# od855.net
KiCad netlist of a schematic drawn in EAGLE
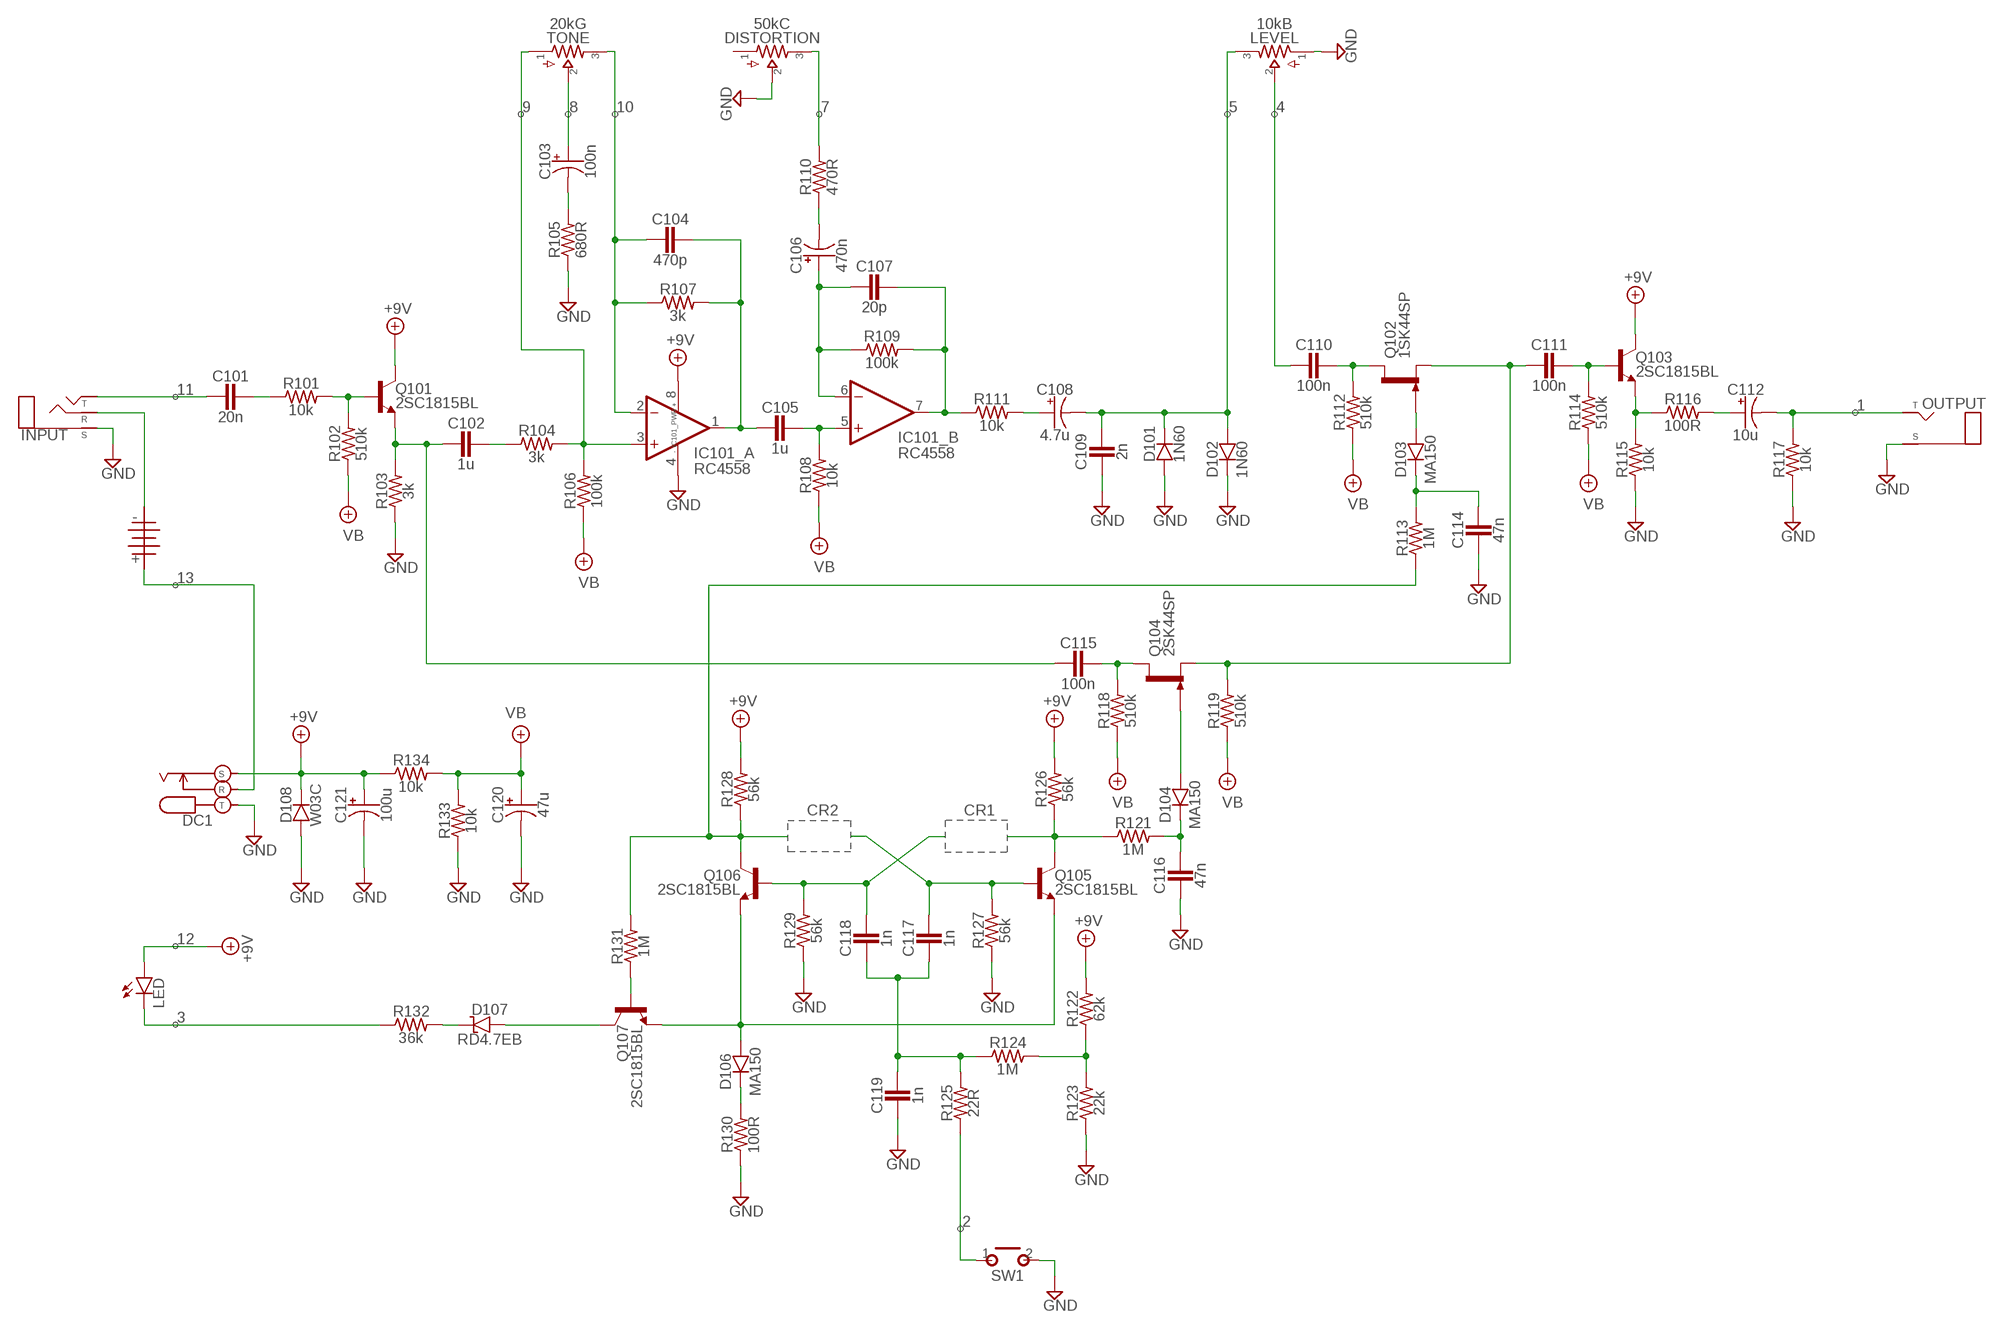
[diagram p0: schematic, sheet 1]

(export (version "E")
  (design (tool "Eeschema 10.0.6"))
  (components
    (comp (ref "11")
      (value "BATTERY")
      (footprint "eagle-import:TWO_PADS")
      (libsource (lib "eagle-import") (part "BATTERY"))
    )
    (comp (ref "C101")
      (value "20n")
      (footprint "eagle-import:BOX_SMALL")
      (libsource (lib "eagle-import") (part "CER/FILMBOX.1"))
    )
    (comp (ref "C102")
      (value "1u")
      (footprint "eagle-import:BOX_SMALL")
      (libsource (lib "eagle-import") (part "CER/FILMBOX.1"))
    )
    (comp (ref "C103")
      (value "100n")
      (footprint "eagle-import:050_020")
      (libsource (lib "eagle-import") (part "0500"))
    )
    (comp (ref "C104")
      (value "470p")
      (footprint "eagle-import:BOX_SMALL")
      (libsource (lib "eagle-import") (part "CER/FILMBOX.1"))
    )
    (comp (ref "C105")
      (value "1u")
      (footprint "eagle-import:BOX_SMALL")
      (libsource (lib "eagle-import") (part "CER/FILMBOX.1"))
    )
    (comp (ref "C106")
      (value "470n")
      (footprint "eagle-import:050_020")
      (libsource (lib "eagle-import") (part "0500"))
    )
    (comp (ref "C107")
      (value "20p")
      (footprint "eagle-import:BOX_SMALL")
      (libsource (lib "eagle-import") (part "CER/FILMBOX.1"))
    )
    (comp (ref "C108")
      (value "4.7u")
      (footprint "eagle-import:050_020")
      (libsource (lib "eagle-import") (part "0500"))
    )
    (comp (ref "C109")
      (value "2n")
      (footprint "eagle-import:BOX_SMALL")
      (libsource (lib "eagle-import") (part "CER/FILMBOX.1"))
    )
    (comp (ref "C110")
      (value "100n")
      (footprint "eagle-import:BOX_SMALL")
      (libsource (lib "eagle-import") (part "CER/FILMBOX.1"))
    )
    (comp (ref "C111")
      (value "100n")
      (footprint "eagle-import:BOX_SMALL")
      (libsource (lib "eagle-import") (part "CER/FILMBOX.1"))
    )
    (comp (ref "C112")
      (value "10u")
      (footprint "eagle-import:050_020")
      (libsource (lib "eagle-import") (part "0500"))
    )
    (comp (ref "C114")
      (value "47n")
      (footprint "eagle-import:BOX_SMALL")
      (libsource (lib "eagle-import") (part "CER/FILMBOX.1"))
    )
    (comp (ref "C115")
      (value "100n")
      (footprint "eagle-import:BOX_SMALL")
      (libsource (lib "eagle-import") (part "CER/FILMBOX.1"))
    )
    (comp (ref "C116")
      (value "47n")
      (footprint "eagle-import:BOX_SMALL")
      (libsource (lib "eagle-import") (part "CER/FILMBOX.1"))
    )
    (comp (ref "C117")
      (value "1n")
      (footprint "eagle-import:BOX_SMALL")
      (libsource (lib "eagle-import") (part "CER/FILMBOX.1"))
    )
    (comp (ref "C118")
      (value "1n")
      (footprint "eagle-import:BOX_SMALL")
      (libsource (lib "eagle-import") (part "CER/FILMBOX.1"))
    )
    (comp (ref "C119")
      (value "1n")
      (footprint "eagle-import:BOX_SMALL")
      (libsource (lib "eagle-import") (part "CER/FILMBOX.1"))
    )
    (comp (ref "C120")
      (value "47u")
      (footprint "eagle-import:050_020")
      (libsource (lib "eagle-import") (part "0500"))
    )
    (comp (ref "C121")
      (value "100u")
      (footprint "eagle-import:050_020")
      (libsource (lib "eagle-import") (part "0500"))
    )
    (comp (ref "D101")
      (value "1N60")
      (footprint "eagle-import:DO35-2")
      (libsource (lib "eagle-import") (part "DO35.2"))
    )
    (comp (ref "D102")
      (value "1N60")
      (footprint "eagle-import:DO35-2")
      (libsource (lib "eagle-import") (part "DO35.2"))
    )
    (comp (ref "D103")
      (value "MA150")
      (footprint "eagle-import:DO35-2")
      (libsource (lib "eagle-import") (part "DO35.2"))
    )
    (comp (ref "D104")
      (value "MA150")
      (footprint "eagle-import:DO35-2")
      (libsource (lib "eagle-import") (part "DO35.2"))
    )
    (comp (ref "D106")
      (value "MA150")
      (footprint "eagle-import:DO35-2")
      (libsource (lib "eagle-import") (part "DO35.2"))
    )
    (comp (ref "D107")
      (value "RD4.7EB")
      (footprint "eagle-import:DO41-2")
      (libsource (lib "eagle-import") (part "ZENER.2"))
    )
    (comp (ref "D108")
      (value "W03C")
      (footprint "eagle-import:DO35-2")
      (libsource (lib "eagle-import") (part "DO35.2"))
    )
    (comp (ref "DC1")
      (value "DCJACK")
      (footprint "eagle-import:DC_KOBICONN")
      (libsource (lib "eagle-import") (part "DC_KOBICONN"))
    )
    (comp (ref "DISTORTION")
      (value "50kC")
      (footprint "eagle-import:16MM")
      (libsource (lib "eagle-import") (part "POTS16MM"))
    )
    (comp (ref "IC101")
      (value "RC4558")
      (footprint "eagle-import:DIL0")
      (libsource (lib "eagle-import") (part "DUALTH"))
    )
    (comp (ref "INPUT")
      (value "STEREO3PADS")
      (footprint "eagle-import:THREEPADS")
      (libsource (lib "eagle-import") (part "STEREO3PADS"))
    )
    (comp (ref "LED")
      (value "LED")
      (footprint "eagle-import:3MM_D")
      (libsource (lib "eagle-import") (part "LED"))
    )
    (comp (ref "LEVEL")
      (value "10kB")
      (footprint "eagle-import:16MM")
      (libsource (lib "eagle-import") (part "POTS16MM"))
    )
    (comp (ref "OUTPUT")
      (value "MONO")
      (footprint "eagle-import:TWO_PADS")
      (libsource (lib "eagle-import") (part "MONO"))
    )
    (comp (ref "Q101")
      (value "2SC1815BL")
      (footprint "eagle-import:TO92-")
      (libsource (lib "eagle-import") (part "2N3904"))
    )
    (comp (ref "Q102")
      (value "1SK44SP")
      (footprint "eagle-import:TO92-")
      (libsource (lib "eagle-import") (part "2N5457"))
    )
    (comp (ref "Q103")
      (value "2SC1815BL")
      (footprint "eagle-import:TO92-")
      (libsource (lib "eagle-import") (part "2N3904"))
    )
    (comp (ref "Q104")
      (value "2SK44SP")
      (footprint "eagle-import:TO92-")
      (libsource (lib "eagle-import") (part "2N5457"))
    )
    (comp (ref "Q105")
      (value "2SC1815BL")
      (footprint "eagle-import:TO92-")
      (libsource (lib "eagle-import") (part "2SC828A"))
    )
    (comp (ref "Q106")
      (value "2SC1815BL")
      (footprint "eagle-import:TO92-")
      (libsource (lib "eagle-import") (part "2SC828A"))
    )
    (comp (ref "Q107")
      (value "2SC1815BL")
      (footprint "eagle-import:TO92-")
      (libsource (lib "eagle-import") (part "2SC828A"))
    )
    (comp (ref "R101")
      (value "10k")
      (footprint "eagle-import:R0207_3")
      (libsource (lib "eagle-import") (part "R_.3B"))
    )
    (comp (ref "R102")
      (value "510k")
      (footprint "eagle-import:R0207_3")
      (libsource (lib "eagle-import") (part "R_.3B"))
    )
    (comp (ref "R103")
      (value "3k")
      (footprint "eagle-import:R0207_3")
      (libsource (lib "eagle-import") (part "R_.3B"))
    )
    (comp (ref "R104")
      (value "3k")
      (footprint "eagle-import:R0207_3")
      (libsource (lib "eagle-import") (part "R_.3B"))
    )
    (comp (ref "R105")
      (value "680R")
      (footprint "eagle-import:R0207_3")
      (libsource (lib "eagle-import") (part "R_.3B"))
    )
    (comp (ref "R106")
      (value "100k")
      (footprint "eagle-import:R0207_3")
      (libsource (lib "eagle-import") (part "R_.3B"))
    )
    (comp (ref "R107")
      (value "3k")
      (footprint "eagle-import:R0207_3")
      (libsource (lib "eagle-import") (part "R_.3B"))
    )
    (comp (ref "R108")
      (value "10k")
      (footprint "eagle-import:R0207_3")
      (libsource (lib "eagle-import") (part "R_.3B"))
    )
    (comp (ref "R109")
      (value "100k")
      (footprint "eagle-import:R0207_3")
      (libsource (lib "eagle-import") (part "R_.3B"))
    )
    (comp (ref "R110")
      (value "470R")
      (footprint "eagle-import:R0207_3")
      (libsource (lib "eagle-import") (part "R_.3B"))
    )
    (comp (ref "R111")
      (value "10k")
      (footprint "eagle-import:R0207_3")
      (libsource (lib "eagle-import") (part "R_.3B"))
    )
    (comp (ref "R112")
      (value "510k")
      (footprint "eagle-import:R0207_3")
      (libsource (lib "eagle-import") (part "R_.3B"))
    )
    (comp (ref "R113")
      (value "1M")
      (footprint "eagle-import:R0207_3")
      (libsource (lib "eagle-import") (part "R_.3B"))
    )
    (comp (ref "R114")
      (value "510k")
      (footprint "eagle-import:R0207_3")
      (libsource (lib "eagle-import") (part "R_.3B"))
    )
    (comp (ref "R115")
      (value "10k")
      (footprint "eagle-import:R0207_3")
      (libsource (lib "eagle-import") (part "R_.3B"))
    )
    (comp (ref "R116")
      (value "100R")
      (footprint "eagle-import:R0207_3")
      (libsource (lib "eagle-import") (part "R_.3B"))
    )
    (comp (ref "R117")
      (value "10k")
      (footprint "eagle-import:R0207_3")
      (libsource (lib "eagle-import") (part "R_.3B"))
    )
    (comp (ref "R118")
      (value "510k")
      (footprint "eagle-import:R0207_3")
      (libsource (lib "eagle-import") (part "R_.3B"))
    )
    (comp (ref "R119")
      (value "510k")
      (footprint "eagle-import:R0207_3")
      (libsource (lib "eagle-import") (part "R_.3B"))
    )
    (comp (ref "R121")
      (value "1M")
      (footprint "eagle-import:R0207_3")
      (libsource (lib "eagle-import") (part "R_.3B"))
    )
    (comp (ref "R122")
      (value "62k")
      (footprint "eagle-import:R0207_3")
      (libsource (lib "eagle-import") (part "R_.3B"))
    )
    (comp (ref "R123")
      (value "22k")
      (footprint "eagle-import:R0207_3")
      (libsource (lib "eagle-import") (part "R_.3B"))
    )
    (comp (ref "R124")
      (value "1M")
      (footprint "eagle-import:R0207_3")
      (libsource (lib "eagle-import") (part "R_.3B"))
    )
    (comp (ref "R125")
      (value "22R")
      (footprint "eagle-import:R0207_3")
      (libsource (lib "eagle-import") (part "R_.3B"))
    )
    (comp (ref "R126")
      (value "56k")
      (footprint "eagle-import:R0207_3")
      (libsource (lib "eagle-import") (part "R_.3B"))
    )
    (comp (ref "R127")
      (value "56k")
      (footprint "eagle-import:R0207_3")
      (libsource (lib "eagle-import") (part "R_.3B"))
    )
    (comp (ref "R128")
      (value "56k")
      (footprint "eagle-import:R0207_3")
      (libsource (lib "eagle-import") (part "R_.3B"))
    )
    (comp (ref "R129")
      (value "56k")
      (footprint "eagle-import:R0207_3")
      (libsource (lib "eagle-import") (part "R_.3B"))
    )
    (comp (ref "R130")
      (value "100R")
      (footprint "eagle-import:R0207_3")
      (libsource (lib "eagle-import") (part "R_.3B"))
    )
    (comp (ref "R131")
      (value "1M")
      (footprint "eagle-import:R0207_3")
      (libsource (lib "eagle-import") (part "R_.3B"))
    )
    (comp (ref "R132")
      (value "36k")
      (footprint "eagle-import:R0207_3")
      (libsource (lib "eagle-import") (part "R_.3B"))
    )
    (comp (ref "R133")
      (value "10k")
      (footprint "eagle-import:R0207_3")
      (libsource (lib "eagle-import") (part "R_.3B"))
    )
    (comp (ref "R134")
      (value "10k")
      (footprint "eagle-import:R0207_3")
      (libsource (lib "eagle-import") (part "R_.3B"))
    )
    (comp (ref "SW1")
      (value "MOMENTARY")
      (footprint "eagle-import:SPST")
      (libsource (lib "eagle-import") (part "MOMENTARY"))
    )
    (comp (ref "TONE")
      (value "20kG")
      (footprint "eagle-import:16MM")
      (libsource (lib "eagle-import") (part "POTS16MM"))
    )
  )
  (nets
    (net (code "1") (name "+9V") (class "Default")
      (node (ref "C121") (pin "+") (pinfunction "+_+") (pintype "passive"))
      (node (ref "D108") (pin "C") (pinfunction "C_C") (pintype "passive"))
      (node (ref "DC1") (pin "S") (pinfunction "S_S") (pintype "bidirectional"))
      (node (ref "IC101") (pin "8") (pinfunction "V+_8") (pintype "power_in"))
      (node (ref "LED") (pin "ANODE") (pinfunction "A_ANODE") (pintype "passive"))
      (node (ref "Q101") (pin "1") (pinfunction "C_1") (pintype "passive"))
      (node (ref "Q103") (pin "1") (pinfunction "C_1") (pintype "passive"))
      (node (ref "R122") (pin "2") (pinfunction "2_2") (pintype "passive"))
      (node (ref "R126") (pin "2") (pinfunction "2_2") (pintype "passive"))
      (node (ref "R128") (pin "2") (pinfunction "2_2") (pintype "passive"))
      (node (ref "R134") (pin "1") (pinfunction "1_1") (pintype "passive"))
    )
    (net (code "2") (name "GND") (class "Default")
      (node (ref "C109") (pin "2") (pinfunction "2_2") (pintype "passive"))
      (node (ref "C114") (pin "2") (pinfunction "2_2") (pintype "passive"))
      (node (ref "C116") (pin "2") (pinfunction "2_2") (pintype "passive"))
      (node (ref "C119") (pin "2") (pinfunction "2_2") (pintype "passive"))
      (node (ref "C120") (pin "-") (pinfunction "-_-") (pintype "passive"))
      (node (ref "C121") (pin "-") (pinfunction "-_-") (pintype "passive"))
      (node (ref "D101") (pin "A") (pinfunction "A_A") (pintype "passive"))
      (node (ref "D102") (pin "C") (pinfunction "C_C") (pintype "passive"))
      (node (ref "D108") (pin "A") (pinfunction "A_A") (pintype "passive"))
      (node (ref "DC1") (pin "T") (pinfunction "T_T") (pintype "bidirectional"))
      (node (ref "DISTORTION") (pin "2") (pinfunction "2_2") (pintype "passive"))
      (node (ref "IC101") (pin "4") (pinfunction "V-_4") (pintype "power_in"))
      (node (ref "INPUT") (pin "SLEEVE") (pinfunction "S_SLEEVE") (pintype "passive"))
      (node (ref "LEVEL") (pin "1") (pinfunction "1_1") (pintype "passive"))
      (node (ref "OUTPUT") (pin "S") (pinfunction "SLEEVE_S") (pintype "passive"))
      (node (ref "R103") (pin "1") (pinfunction "1_1") (pintype "passive"))
      (node (ref "R105") (pin "1") (pinfunction "1_1") (pintype "passive"))
      (node (ref "R115") (pin "1") (pinfunction "1_1") (pintype "passive"))
      (node (ref "R117") (pin "1") (pinfunction "1_1") (pintype "passive"))
      (node (ref "R123") (pin "1") (pinfunction "1_1") (pintype "passive"))
      (node (ref "R127") (pin "1") (pinfunction "1_1") (pintype "passive"))
      (node (ref "R129") (pin "1") (pinfunction "1_1") (pintype "passive"))
      (node (ref "R130") (pin "1") (pinfunction "1_1") (pintype "passive"))
      (node (ref "R133") (pin "1") (pinfunction "1_1") (pintype "passive"))
      (node (ref "SW1") (pin "2") (pinfunction "S_2") (pintype "passive"))
    )
    (net (code "3") (name "Net-(11-P$1)") (class "Default")
      (node (ref "11") (pin "T") (pinfunction "P$1_T") (pintype "bidirectional"))
      (node (ref "DC1") (pin "R") (pinfunction "R_R") (pintype "bidirectional"))
    )
    (net (code "4") (name "Net-(11-P$2)") (class "Default")
      (node (ref "11") (pin "S") (pinfunction "P$2_S") (pintype "bidirectional"))
      (node (ref "INPUT") (pin "RING") (pinfunction "R_RING") (pintype "passive"))
    )
    (net (code "5") (name "Net-(C101-Pad1)") (class "Default")
      (node (ref "C101") (pin "1") (pinfunction "1_1") (pintype "passive"))
      (node (ref "R101") (pin "1") (pinfunction "1_1") (pintype "passive"))
    )
    (net (code "6") (name "Net-(C102-Pad1)") (class "Default")
      (node (ref "C102") (pin "1") (pinfunction "1_1") (pintype "passive"))
      (node (ref "R104") (pin "1") (pinfunction "1_1") (pintype "passive"))
    )
    (net (code "7") (name "Net-(C103-Pad+)") (class "Default")
      (node (ref "C103") (pin "+") (pinfunction "+_+") (pintype "passive"))
      (node (ref "TONE") (pin "2") (pinfunction "2_2") (pintype "passive"))
    )
    (net (code "8") (name "Net-(C103-Pad-)") (class "Default")
      (node (ref "C103") (pin "-") (pinfunction "-_-") (pintype "passive"))
      (node (ref "R105") (pin "2") (pinfunction "2_2") (pintype "passive"))
    )
    (net (code "9") (name "Net-(C106-Pad-)") (class "Default")
      (node (ref "C106") (pin "-") (pinfunction "-_-") (pintype "passive"))
      (node (ref "R110") (pin "1") (pinfunction "1_1") (pintype "passive"))
    )
    (net (code "10") (name "Net-(C108-Pad+)") (class "Default")
      (node (ref "C108") (pin "+") (pinfunction "+_+") (pintype "passive"))
      (node (ref "R111") (pin "2") (pinfunction "2_2") (pintype "passive"))
    )
    (net (code "11") (name "Net-(C108-Pad-)") (class "Default")
      (node (ref "C108") (pin "-") (pinfunction "-_-") (pintype "passive"))
      (node (ref "C109") (pin "1") (pinfunction "1_1") (pintype "passive"))
      (node (ref "D101") (pin "C") (pinfunction "C_C") (pintype "passive"))
      (node (ref "D102") (pin "A") (pinfunction "A_A") (pintype "passive"))
      (node (ref "LEVEL") (pin "3") (pinfunction "3_3") (pintype "passive"))
    )
    (net (code "12") (name "Net-(C110-Pad2)") (class "Default")
      (node (ref "C110") (pin "2") (pinfunction "2_2") (pintype "passive"))
      (node (ref "LEVEL") (pin "2") (pinfunction "2_2") (pintype "passive"))
    )
    (net (code "13") (name "Net-(C112-Pad+)") (class "Default")
      (node (ref "C112") (pin "+") (pinfunction "+_+") (pintype "passive"))
      (node (ref "R116") (pin "2") (pinfunction "2_2") (pintype "passive"))
    )
    (net (code "14") (name "Net-(C114-Pad1)") (class "Default")
      (node (ref "C114") (pin "1") (pinfunction "1_1") (pintype "passive"))
      (node (ref "D103") (pin "C") (pinfunction "C_C") (pintype "passive"))
      (node (ref "R113") (pin "2") (pinfunction "2_2") (pintype "passive"))
    )
    (net (code "15") (name "Net-(C116-Pad1)") (class "Default")
      (node (ref "C116") (pin "1") (pinfunction "1_1") (pintype "passive"))
      (node (ref "D104") (pin "C") (pinfunction "C_C") (pintype "passive"))
      (node (ref "R121") (pin "2") (pinfunction "2_2") (pintype "passive"))
    )
    (net (code "16") (name "Net-(C117-Pad2)") (class "Default")
      (node (ref "C117") (pin "2") (pinfunction "2_2") (pintype "passive"))
      (node (ref "C118") (pin "2") (pinfunction "2_2") (pintype "passive"))
      (node (ref "C119") (pin "1") (pinfunction "1_1") (pintype "passive"))
      (node (ref "R124") (pin "1") (pinfunction "1_1") (pintype "passive"))
      (node (ref "R125") (pin "2") (pinfunction "2_2") (pintype "passive"))
    )
    (net (code "17") (name "Net-(D106-PadC)") (class "Default")
      (node (ref "D106") (pin "C") (pinfunction "C_C") (pintype "passive"))
      (node (ref "R130") (pin "2") (pinfunction "2_2") (pintype "passive"))
    )
    (net (code "18") (name "Net-(D107-PadC)") (class "Default")
      (node (ref "D107") (pin "C") (pinfunction "C_C") (pintype "passive"))
      (node (ref "R132") (pin "2") (pinfunction "2_2") (pintype "passive"))
    )
    (net (code "19") (name "Net-(DISTORTION-Pad3)") (class "Default")
      (node (ref "DISTORTION") (pin "3") (pinfunction "3_3") (pintype "passive"))
      (node (ref "R110") (pin "2") (pinfunction "2_2") (pintype "passive"))
    )
    (net (code "20") (name "Net-(IC101A-+IN)") (class "Default")
      (node (ref "IC101") (pin "3") (pinfunction "+IN_3") (pintype "input"))
      (node (ref "R104") (pin "2") (pinfunction "2_2") (pintype "passive"))
      (node (ref "R106") (pin "2") (pinfunction "2_2") (pintype "passive"))
      (node (ref "TONE") (pin "1") (pinfunction "1_1") (pintype "passive"))
    )
    (net (code "21") (name "Net-(IC101A--IN)") (class "Default")
      (node (ref "C104") (pin "2") (pinfunction "2_2") (pintype "passive"))
      (node (ref "IC101") (pin "2") (pinfunction "-IN_2") (pintype "input"))
      (node (ref "R107") (pin "1") (pinfunction "1_1") (pintype "passive"))
      (node (ref "TONE") (pin "3") (pinfunction "3_3") (pintype "passive"))
    )
    (net (code "22") (name "Net-(IC101A-OUT)") (class "Default")
      (node (ref "C104") (pin "1") (pinfunction "1_1") (pintype "passive"))
      (node (ref "C105") (pin "2") (pinfunction "2_2") (pintype "passive"))
      (node (ref "IC101") (pin "1") (pinfunction "OUT_1") (pintype "output"))
      (node (ref "R107") (pin "2") (pinfunction "2_2") (pintype "passive"))
    )
    (net (code "23") (name "Net-(IC101B-+IN)") (class "Default")
      (node (ref "C105") (pin "1") (pinfunction "1_1") (pintype "passive"))
      (node (ref "IC101") (pin "5") (pinfunction "+IN_5") (pintype "input"))
      (node (ref "R108") (pin "2") (pinfunction "2_2") (pintype "passive"))
    )
    (net (code "24") (name "Net-(IC101B--IN)") (class "Default")
      (node (ref "C106") (pin "+") (pinfunction "+_+") (pintype "passive"))
      (node (ref "C107") (pin "2") (pinfunction "2_2") (pintype "passive"))
      (node (ref "IC101") (pin "6") (pinfunction "-IN_6") (pintype "input"))
      (node (ref "R109") (pin "1") (pinfunction "1_1") (pintype "passive"))
    )
    (net (code "25") (name "Net-(IC101B-OUT)") (class "Default")
      (node (ref "C107") (pin "1") (pinfunction "1_1") (pintype "passive"))
      (node (ref "IC101") (pin "7") (pinfunction "OUT_7") (pintype "output"))
      (node (ref "R109") (pin "2") (pinfunction "2_2") (pintype "passive"))
      (node (ref "R111") (pin "1") (pinfunction "1_1") (pintype "passive"))
    )
    (net (code "26") (name "Net-(INPUT-T)") (class "Default")
      (node (ref "C101") (pin "2") (pinfunction "2_2") (pintype "passive"))
      (node (ref "INPUT") (pin "TIP") (pinfunction "T_TIP") (pintype "passive"))
    )
    (net (code "27") (name "Net-(LED-C)") (class "Default")
      (node (ref "LED") (pin "P$1") (pinfunction "C_P$1") (pintype "passive"))
      (node (ref "R132") (pin "1") (pinfunction "1_1") (pintype "passive"))
    )
    (net (code "28") (name "Net-(OUTPUT-TIP)") (class "Default")
      (node (ref "C112") (pin "-") (pinfunction "-_-") (pintype "passive"))
      (node (ref "OUTPUT") (pin "T") (pinfunction "TIP_T") (pintype "passive"))
      (node (ref "R117") (pin "2") (pinfunction "2_2") (pintype "passive"))
    )
    (net (code "29") (name "Net-(Q101-B)") (class "Default")
      (node (ref "Q101") (pin "2") (pinfunction "B_2") (pintype "passive"))
      (node (ref "R101") (pin "2") (pinfunction "2_2") (pintype "passive"))
      (node (ref "R102") (pin "2") (pinfunction "2_2") (pintype "passive"))
    )
    (net (code "30") (name "Net-(Q101-E)") (class "Default")
      (node (ref "C102") (pin "2") (pinfunction "2_2") (pintype "passive"))
      (node (ref "C115") (pin "2") (pinfunction "2_2") (pintype "passive"))
      (node (ref "Q101") (pin "3") (pinfunction "E_3") (pintype "passive"))
      (node (ref "R103") (pin "2") (pinfunction "2_2") (pintype "passive"))
    )
    (net (code "31") (name "Net-(Q102-D)") (class "Default")
      (node (ref "C110") (pin "1") (pinfunction "1_1") (pintype "passive"))
      (node (ref "Q102") (pin "3") (pinfunction "D_3") (pintype "passive"))
      (node (ref "R112") (pin "2") (pinfunction "2_2") (pintype "passive"))
    )
    (net (code "32") (name "Net-(Q102-G)") (class "Default")
      (node (ref "D103") (pin "A") (pinfunction "A_A") (pintype "passive"))
      (node (ref "Q102") (pin "1") (pinfunction "G_1") (pintype "passive"))
    )
    (net (code "33") (name "Net-(Q102-S)") (class "Default")
      (node (ref "C111") (pin "2") (pinfunction "2_2") (pintype "passive"))
      (node (ref "Q102") (pin "2") (pinfunction "S_2") (pintype "passive"))
      (node (ref "Q104") (pin "2") (pinfunction "S_2") (pintype "passive"))
      (node (ref "R119") (pin "2") (pinfunction "2_2") (pintype "passive"))
    )
    (net (code "34") (name "Net-(Q103-B)") (class "Default")
      (node (ref "C111") (pin "1") (pinfunction "1_1") (pintype "passive"))
      (node (ref "Q103") (pin "2") (pinfunction "B_2") (pintype "passive"))
      (node (ref "R114") (pin "2") (pinfunction "2_2") (pintype "passive"))
    )
    (net (code "35") (name "Net-(Q103-E)") (class "Default")
      (node (ref "Q103") (pin "3") (pinfunction "E_3") (pintype "passive"))
      (node (ref "R115") (pin "2") (pinfunction "2_2") (pintype "passive"))
      (node (ref "R116") (pin "1") (pinfunction "1_1") (pintype "passive"))
    )
    (net (code "36") (name "Net-(Q104-D)") (class "Default")
      (node (ref "C115") (pin "1") (pinfunction "1_1") (pintype "passive"))
      (node (ref "Q104") (pin "3") (pinfunction "D_3") (pintype "passive"))
      (node (ref "R118") (pin "2") (pinfunction "2_2") (pintype "passive"))
    )
    (net (code "37") (name "Net-(Q104-G)") (class "Default")
      (node (ref "D104") (pin "A") (pinfunction "A_A") (pintype "passive"))
      (node (ref "Q104") (pin "1") (pinfunction "G_1") (pintype "passive"))
    )
    (net (code "38") (name "Net-(Q105-B)") (class "Default")
      (node (ref "C117") (pin "1") (pinfunction "1_1") (pintype "passive"))
      (node (ref "Q105") (pin "1") (pinfunction "B_1") (pintype "passive"))
      (node (ref "R127") (pin "2") (pinfunction "2_2") (pintype "passive"))
    )
    (net (code "39") (name "Net-(Q105-C)") (class "Default")
      (node (ref "Q105") (pin "2") (pinfunction "C_2") (pintype "passive"))
      (node (ref "R121") (pin "1") (pinfunction "1_1") (pintype "passive"))
      (node (ref "R126") (pin "1") (pinfunction "1_1") (pintype "passive"))
    )
    (net (code "40") (name "Net-(Q105-E)") (class "Default")
      (node (ref "D106") (pin "A") (pinfunction "A_A") (pintype "passive"))
      (node (ref "Q105") (pin "3") (pinfunction "E_3") (pintype "passive"))
      (node (ref "Q106") (pin "3") (pinfunction "E_3") (pintype "passive"))
      (node (ref "Q107") (pin "3") (pinfunction "E_3") (pintype "passive"))
    )
    (net (code "41") (name "Net-(Q106-B)") (class "Default")
      (node (ref "C118") (pin "1") (pinfunction "1_1") (pintype "passive"))
      (node (ref "Q106") (pin "1") (pinfunction "B_1") (pintype "passive"))
      (node (ref "R129") (pin "2") (pinfunction "2_2") (pintype "passive"))
    )
    (net (code "42") (name "Net-(Q106-C)") (class "Default")
      (node (ref "Q106") (pin "2") (pinfunction "C_2") (pintype "passive"))
      (node (ref "R113") (pin "1") (pinfunction "1_1") (pintype "passive"))
      (node (ref "R128") (pin "1") (pinfunction "1_1") (pintype "passive"))
      (node (ref "R131") (pin "2") (pinfunction "2_2") (pintype "passive"))
    )
    (net (code "43") (name "Net-(Q107-B)") (class "Default")
      (node (ref "Q107") (pin "1") (pinfunction "B_1") (pintype "passive"))
      (node (ref "R131") (pin "1") (pinfunction "1_1") (pintype "passive"))
    )
    (net (code "44") (name "Net-(Q107-C)") (class "Default")
      (node (ref "D107") (pin "A") (pinfunction "A_A") (pintype "passive"))
      (node (ref "Q107") (pin "2") (pinfunction "C_2") (pintype "passive"))
    )
    (net (code "45") (name "Net-(R122-Pad1)") (class "Default")
      (node (ref "R122") (pin "1") (pinfunction "1_1") (pintype "passive"))
      (node (ref "R123") (pin "2") (pinfunction "2_2") (pintype "passive"))
      (node (ref "R124") (pin "2") (pinfunction "2_2") (pintype "passive"))
    )
    (net (code "46") (name "Net-(SW1-P)") (class "Default")
      (node (ref "R125") (pin "1") (pinfunction "1_1") (pintype "passive"))
      (node (ref "SW1") (pin "1") (pinfunction "P_1") (pintype "passive"))
    )
    (net (code "47") (name "VB") (class "Default")
      (node (ref "C120") (pin "+") (pinfunction "+_+") (pintype "passive"))
      (node (ref "R102") (pin "1") (pinfunction "1_1") (pintype "passive"))
      (node (ref "R106") (pin "1") (pinfunction "1_1") (pintype "passive"))
      (node (ref "R108") (pin "1") (pinfunction "1_1") (pintype "passive"))
      (node (ref "R112") (pin "1") (pinfunction "1_1") (pintype "passive"))
      (node (ref "R114") (pin "1") (pinfunction "1_1") (pintype "passive"))
      (node (ref "R118") (pin "1") (pinfunction "1_1") (pintype "passive"))
      (node (ref "R119") (pin "1") (pinfunction "1_1") (pintype "passive"))
      (node (ref "R133") (pin "2") (pinfunction "2_2") (pintype "passive"))
      (node (ref "R134") (pin "2") (pinfunction "2_2") (pintype "passive"))
    )
    (net (code "48") (name "unconnected-(DISTORTION-Pad1)") (class "Default")
      (node (ref "DISTORTION") (pin "1") (pinfunction "1_1") (pintype "passive"))
    )
  )
)
